# J3.net
KiCad netlist of a schematic drawn in Altium Designer
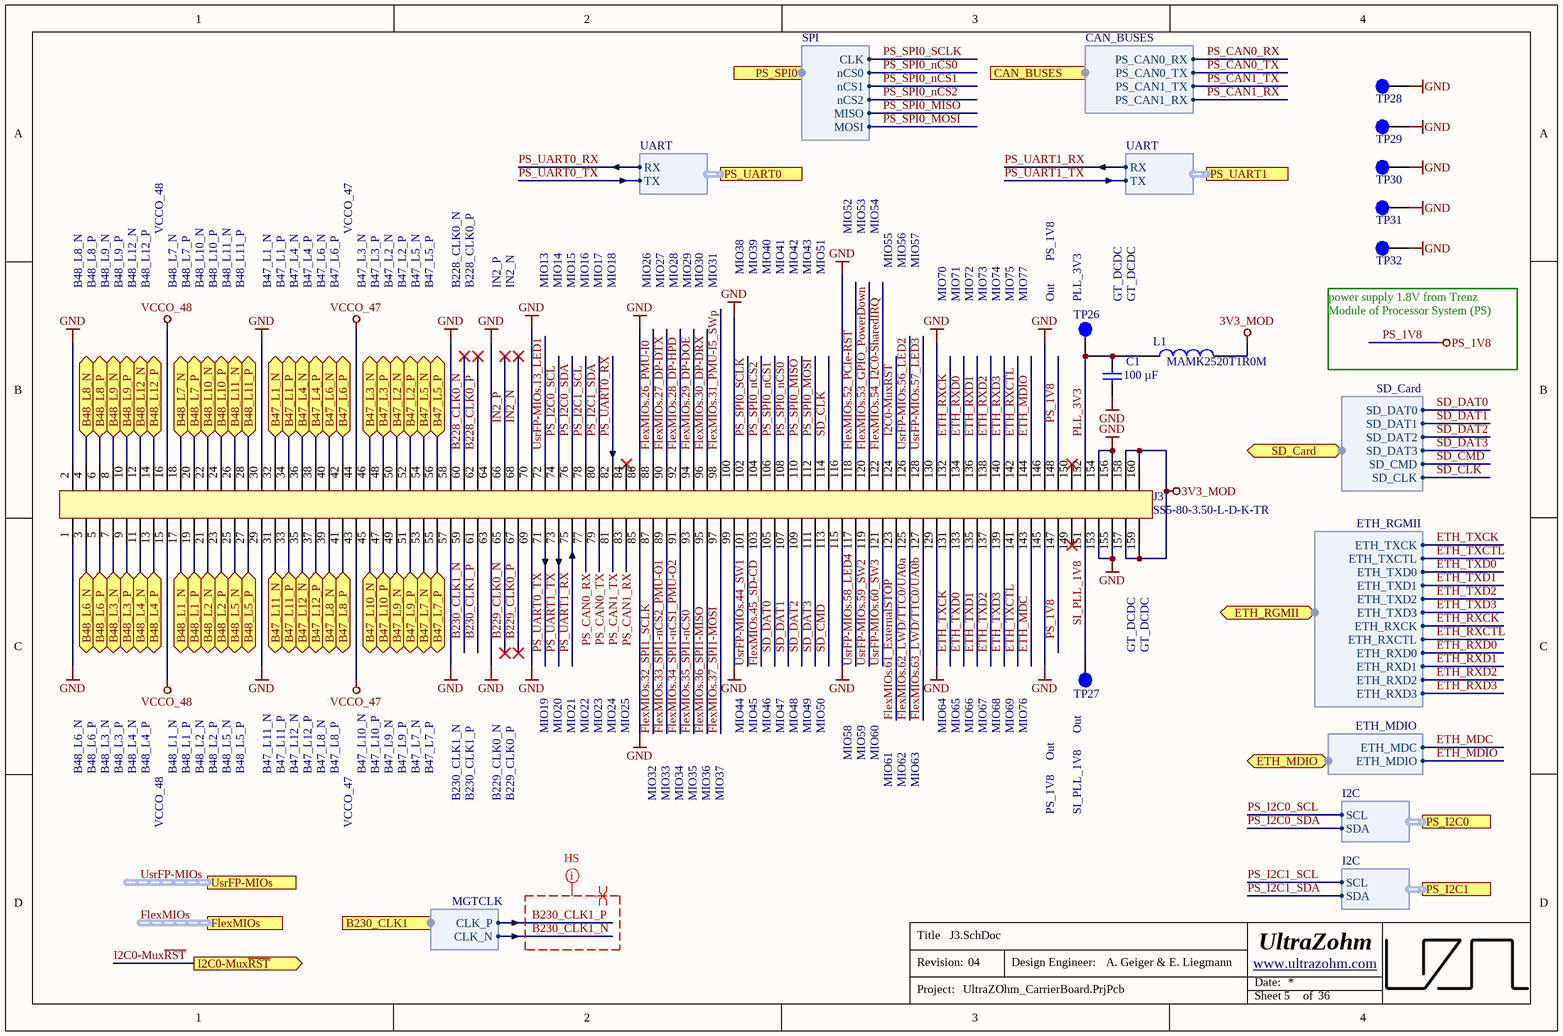
[diagram p0: J3.SchDoc]

(export (version "E")
  (design (tool "Eeschema 10.0.6"))
  (components
    (comp (ref "C1")
      (value "100 µF")
      (footprint "C_1206_TE")
      (description "6.3V 100uF X5R ±20% 1206 Multilayer Ceramic Capacitors MLCC")
      (fields
        (field (name "TOLERANCE") "20%")
        (field (name "MANUFACTURER PART NUMBER") "CL31A107MQHNNNE")
        (field (name "CREATED FROM") "MGeier")
      )
      (libsource (lib "user") (part "CAP-NP"))
    )
    (comp (ref "J3")
      (value "SS5-80-3.50-L-D-K-TR")
      (footprint "SS5-80-3.50-L-D-K-TR")
      (description "0.5 mm Ultra Fine Pitch Socket REF192552-01, 160 Pins")
      (fields
        (field (name "MANUFACTURER") "SAMTEC")
        (field (name "LCSC PART NUMBER") "C5292077")
        (field (name "CREATED FROM") "MGremer")
      )
      (libsource (lib "user") (part "SS5-80-3.50-L-D-K-TR"))
    )
    (comp (ref "L1")
      (value "MAMK2520T1R0M")
      (footprint "INDC2520X120N")
      (description "1uH @2MHz ±20%, 2.7A, 59mOhm, 5040")
      (fields
        (field (name "MF") "EPCOS / TDK")
        (field (name "MPN") "B82464G4154M")
        (field (name "CREATED FROM") "FRosner")
      )
      (libsource (lib "user") (part "B82464G4154M"))
    )
    (comp (ref "TP26") (value "Testpoint 1mm") (footprint "TP_1mm") (libsource (lib "TE") (part "TP")))
    (comp (ref "TP27") (value "Testpoint 1mm") (footprint "TP_1mm") (libsource (lib "TE") (part "TP")))
    (comp (ref "TP28") (value "Testpoint 1mm") (footprint "TP_1mm") (libsource (lib "TE") (part "TP")))
    (comp (ref "TP29") (value "Testpoint 1mm") (footprint "TP_1mm") (libsource (lib "TE") (part "TP")))
    (comp (ref "TP30") (value "Testpoint 1mm") (footprint "TP_1mm") (libsource (lib "TE") (part "TP")))
    (comp (ref "TP31") (value "Testpoint 1mm") (footprint "TP_1mm") (libsource (lib "TE") (part "TP")))
    (comp (ref "TP32") (value "Testpoint 1mm") (footprint "TP_1mm") (libsource (lib "TE") (part "TP")))
  )
  (nets
    (net (code "10") (name "/B47_L1_N") (class "Default")
      (node (ref "J3") (pin "32") (pinfunction "32_32") (pintype "passive"))
    )
    (net (code "11") (name "/B47_L1_P") (class "Default")
      (node (ref "J3") (pin "34") (pinfunction "34_34") (pintype "passive"))
    )
    (net (code "12") (name "/B47_L2_N") (class "Default")
      (node (ref "J3") (pin "50") (pinfunction "50_50") (pintype "passive"))
    )
    (net (code "13") (name "/B47_L2_P") (class "Default")
      (node (ref "J3") (pin "52") (pinfunction "52_52") (pintype "passive"))
    )
    (net (code "14") (name "/B47_L3_N") (class "Default")
      (node (ref "J3") (pin "46") (pinfunction "46_46") (pintype "passive"))
    )
    (net (code "15") (name "/B47_L3_P") (class "Default")
      (node (ref "J3") (pin "48") (pinfunction "48_48") (pintype "passive"))
    )
    (net (code "16") (name "/B47_L4_N") (class "Default")
      (node (ref "J3") (pin "36") (pinfunction "36_36") (pintype "passive"))
    )
    (net (code "17") (name "/B47_L4_P") (class "Default")
      (node (ref "J3") (pin "38") (pinfunction "38_38") (pintype "passive"))
    )
    (net (code "18") (name "/B47_L5_N") (class "Default")
      (node (ref "J3") (pin "54") (pinfunction "54_54") (pintype "passive"))
    )
    (net (code "19") (name "/B47_L5_P") (class "Default")
      (node (ref "J3") (pin "56") (pinfunction "56_56") (pintype "passive"))
    )
    (net (code "20") (name "/B47_L6_N") (class "Default")
      (node (ref "J3") (pin "40") (pinfunction "40_40") (pintype "passive"))
    )
    (net (code "21") (name "/B47_L6_P") (class "Default")
      (node (ref "J3") (pin "42") (pinfunction "42_42") (pintype "passive"))
    )
    (net (code "22") (name "/B47_L7_N") (class "Default")
      (node (ref "J3") (pin "53") (pinfunction "53_53") (pintype "passive"))
    )
    (net (code "23") (name "/B47_L7_P") (class "Default")
      (node (ref "J3") (pin "55") (pinfunction "55_55") (pintype "passive"))
    )
    (net (code "24") (name "/B47_L8_N") (class "Default")
      (node (ref "J3") (pin "39") (pinfunction "39_39") (pintype "passive"))
    )
    (net (code "25") (name "/B47_L8_P") (class "Default")
      (node (ref "J3") (pin "41") (pinfunction "41_41") (pintype "passive"))
    )
    (net (code "26") (name "/B47_L9_N") (class "Default")
      (node (ref "J3") (pin "49") (pinfunction "49_49") (pintype "passive"))
    )
    (net (code "27") (name "/B47_L9_P") (class "Default")
      (node (ref "J3") (pin "51") (pinfunction "51_51") (pintype "passive"))
    )
    (net (code "28") (name "/B47_L10_N") (class "Default")
      (node (ref "J3") (pin "45") (pinfunction "45_45") (pintype "passive"))
    )
    (net (code "29") (name "/B47_L10_P") (class "Default")
      (node (ref "J3") (pin "47") (pinfunction "47_47") (pintype "passive"))
    )
    (net (code "30") (name "/B47_L11_N") (class "Default")
      (node (ref "J3") (pin "31") (pinfunction "31_31") (pintype "passive"))
    )
    (net (code "31") (name "/B47_L11_P") (class "Default")
      (node (ref "J3") (pin "33") (pinfunction "33_33") (pintype "passive"))
    )
    (net (code "32") (name "/B47_L12_N") (class "Default")
      (node (ref "J3") (pin "35") (pinfunction "35_35") (pintype "passive"))
    )
    (net (code "33") (name "/B47_L12_P") (class "Default")
      (node (ref "J3") (pin "37") (pinfunction "37_37") (pintype "passive"))
    )
    (net (code "34") (name "/B48_L1_N") (class "Default")
      (node (ref "J3") (pin "17") (pinfunction "17_17") (pintype "passive"))
    )
    (net (code "35") (name "/B48_L1_P") (class "Default")
      (node (ref "J3") (pin "19") (pinfunction "19_19") (pintype "passive"))
    )
    (net (code "36") (name "/B48_L2_N") (class "Default")
      (node (ref "J3") (pin "21") (pinfunction "21_21") (pintype "passive"))
    )
    (net (code "37") (name "/B48_L2_P") (class "Default")
      (node (ref "J3") (pin "23") (pinfunction "23_23") (pintype "passive"))
    )
    (net (code "38") (name "/B48_L3_N") (class "Default")
      (node (ref "J3") (pin "7") (pinfunction "7_7") (pintype "passive"))
    )
    (net (code "39") (name "/B48_L3_P") (class "Default")
      (node (ref "J3") (pin "9") (pinfunction "9_9") (pintype "passive"))
    )
    (net (code "40") (name "/B48_L4_N") (class "Default")
      (node (ref "J3") (pin "11") (pinfunction "11_11") (pintype "passive"))
    )
    (net (code "41") (name "/B48_L4_P") (class "Default")
      (node (ref "J3") (pin "13") (pinfunction "13_13") (pintype "passive"))
    )
    (net (code "42") (name "/B48_L5_N") (class "Default")
      (node (ref "J3") (pin "25") (pinfunction "25_25") (pintype "passive"))
    )
    (net (code "43") (name "/B48_L5_P") (class "Default")
      (node (ref "J3") (pin "27") (pinfunction "27_27") (pintype "passive"))
    )
    (net (code "44") (name "/B48_L6_N") (class "Default")
      (node (ref "J3") (pin "3") (pinfunction "3_3") (pintype "passive"))
    )
    (net (code "45") (name "/B48_L6_P") (class "Default")
      (node (ref "J3") (pin "5") (pinfunction "5_5") (pintype "passive"))
    )
    (net (code "46") (name "/B48_L7_N") (class "Default")
      (node (ref "J3") (pin "18") (pinfunction "18_18") (pintype "passive"))
    )
    (net (code "47") (name "/B48_L7_P") (class "Default")
      (node (ref "J3") (pin "20") (pinfunction "20_20") (pintype "passive"))
    )
    (net (code "48") (name "/B48_L8_N") (class "Default")
      (node (ref "J3") (pin "4") (pinfunction "4_4") (pintype "passive"))
    )
    (net (code "49") (name "/B48_L8_P") (class "Default")
      (node (ref "J3") (pin "6") (pinfunction "6_6") (pintype "passive"))
    )
    (net (code "50") (name "/B48_L9_N") (class "Default")
      (node (ref "J3") (pin "8") (pinfunction "8_8") (pintype "passive"))
    )
    (net (code "51") (name "/B48_L9_P") (class "Default")
      (node (ref "J3") (pin "10") (pinfunction "10_10") (pintype "passive"))
    )
    (net (code "52") (name "/B48_L10_N") (class "Default")
      (node (ref "J3") (pin "22") (pinfunction "22_22") (pintype "passive"))
    )
    (net (code "53") (name "/B48_L10_P") (class "Default")
      (node (ref "J3") (pin "24") (pinfunction "24_24") (pintype "passive"))
    )
    (net (code "54") (name "/B48_L11_N") (class "Default")
      (node (ref "J3") (pin "26") (pinfunction "26_26") (pintype "passive"))
    )
    (net (code "55") (name "/B48_L11_P") (class "Default")
      (node (ref "J3") (pin "28") (pinfunction "28_28") (pintype "passive"))
    )
    (net (code "56") (name "/B48_L12_N") (class "Default")
      (node (ref "J3") (pin "12") (pinfunction "12_12") (pintype "passive"))
    )
    (net (code "57") (name "/B48_L12_P") (class "Default")
      (node (ref "J3") (pin "14") (pinfunction "14_14") (pintype "passive"))
    )
    (net (code "58") (name "/B228_CLK0_N") (class "Default")
      (node (ref "J3") (pin "60") (pinfunction "60_60") (pintype "passive+no_connect"))
    )
    (net (code "59") (name "/B228_CLK0_P") (class "Default")
      (node (ref "J3") (pin "62") (pinfunction "62_62") (pintype "passive+no_connect"))
    )
    (net (code "60") (name "/B229_CLK0_N") (class "Default")
      (node (ref "J3") (pin "65") (pinfunction "65_65") (pintype "passive+no_connect"))
    )
    (net (code "61") (name "/B229_CLK0_P") (class "Default")
      (node (ref "J3") (pin "67") (pinfunction "67_67") (pintype "passive+no_connect"))
    )
    (net (code "62") (name "/B230_CLK1_N") (class "Default")
      (node (ref "J3") (pin "59") (pinfunction "59_59") (pintype "passive"))
    )
    (net (code "63") (name "/B230_CLK1_P") (class "Default")
      (node (ref "J3") (pin "61") (pinfunction "61_61") (pintype "passive"))
    )
    (net (code "64") (name "/ETH_MDC") (class "Default")
      (node (ref "J3") (pin "143") (pinfunction "143_143") (pintype "passive"))
    )
    (net (code "65") (name "/ETH_MDIO") (class "Default")
      (node (ref "J3") (pin "144") (pinfunction "144_144") (pintype "passive"))
    )
    (net (code "66") (name "/ETH_RXCK") (class "Default")
      (node (ref "J3") (pin "132") (pinfunction "132_132") (pintype "passive"))
    )
    (net (code "67") (name "/ETH_RXCTL") (class "Default")
      (node (ref "J3") (pin "142") (pinfunction "142_142") (pintype "passive"))
    )
    (net (code "68") (name "/ETH_RXD0") (class "Default")
      (node (ref "J3") (pin "134") (pinfunction "134_134") (pintype "passive"))
    )
    (net (code "69") (name "/ETH_RXD1") (class "Default")
      (node (ref "J3") (pin "136") (pinfunction "136_136") (pintype "passive"))
    )
    (net (code "70") (name "/ETH_RXD2") (class "Default")
      (node (ref "J3") (pin "138") (pinfunction "138_138") (pintype "passive"))
    )
    (net (code "71") (name "/ETH_RXD3") (class "Default")
      (node (ref "J3") (pin "140") (pinfunction "140_140") (pintype "passive"))
    )
    (net (code "72") (name "/ETH_TXCK") (class "Default")
      (node (ref "J3") (pin "131") (pinfunction "131_131") (pintype "passive"))
    )
    (net (code "73") (name "/ETH_TXCTL") (class "Default")
      (node (ref "J3") (pin "141") (pinfunction "141_141") (pintype "passive"))
    )
    (net (code "74") (name "/ETH_TXD0") (class "Default")
      (node (ref "J3") (pin "133") (pinfunction "133_133") (pintype "passive"))
    )
    (net (code "75") (name "/ETH_TXD1") (class "Default")
      (node (ref "J3") (pin "135") (pinfunction "135_135") (pintype "passive"))
    )
    (net (code "76") (name "/ETH_TXD2") (class "Default")
      (node (ref "J3") (pin "137") (pinfunction "137_137") (pintype "passive"))
    )
    (net (code "77") (name "/ETH_TXD3") (class "Default")
      (node (ref "J3") (pin "139") (pinfunction "139_139") (pintype "passive"))
    )
    (net (code "78") (name "/FlexMIOs.26_PMU-I0") (class "Default")
      (node (ref "J3") (pin "88") (pinfunction "88_88") (pintype "passive"))
    )
    (net (code "79") (name "/FlexMIOs.27_DP-DTX") (class "Default")
      (node (ref "J3") (pin "90") (pinfunction "90_90") (pintype "passive"))
    )
    (net (code "80") (name "/FlexMIOs.28_DP-HPD") (class "Default")
      (node (ref "J3") (pin "92") (pinfunction "92_92") (pintype "passive"))
    )
    (net (code "81") (name "/FlexMIOs.29_DP-DOE") (class "Default")
      (node (ref "J3") (pin "94") (pinfunction "94_94") (pintype "passive"))
    )
    (net (code "82") (name "/FlexMIOs.30_DP-DRX") (class "Default")
      (node (ref "J3") (pin "96") (pinfunction "96_96") (pintype "passive"))
    )
    (net (code "83") (name "/FlexMIOs.31_PMU-I5_SWp") (class "Default")
      (node (ref "J3") (pin "98") (pinfunction "98_98") (pintype "passive"))
    )
    (net (code "84") (name "/FlexMIOs.32_SPI1_SCLK") (class "Default")
      (node (ref "J3") (pin "87") (pinfunction "87_87") (pintype "passive"))
    )
    (net (code "85") (name "/FlexMIOs.33_SPI1-nCS2_PMU-O1") (class "Default")
      (node (ref "J3") (pin "89") (pinfunction "89_89") (pintype "passive"))
    )
    (net (code "86") (name "/FlexMIOs.34_SPI1-nCS1_PMU-O2") (class "Default")
      (node (ref "J3") (pin "91") (pinfunction "91_91") (pintype "passive"))
    )
    (net (code "87") (name "/FlexMIOs.35_SPI1-nCS0") (class "Default")
      (node (ref "J3") (pin "93") (pinfunction "93_93") (pintype "passive"))
    )
    (net (code "88") (name "/FlexMIOs.36_SPI1-MISO") (class "Default")
      (node (ref "J3") (pin "95") (pinfunction "95_95") (pintype "passive"))
    )
    (net (code "89") (name "/FlexMIOs.37_SPI1-MOSI") (class "Default")
      (node (ref "J3") (pin "97") (pinfunction "97_97") (pintype "passive"))
    )
    (net (code "90") (name "/FlexMIOs.45_SD-CD") (class "Default")
      (node (ref "J3") (pin "103") (pinfunction "103_103") (pintype "passive"))
    )
    (net (code "91") (name "/FlexMIOs.52_PCIe-~{RST}") (class "Default")
      (node (ref "J3") (pin "118") (pinfunction "118_118") (pintype "passive"))
    )
    (net (code "92") (name "/FlexMIOs.53_GPIO_PowerDown") (class "Default")
      (node (ref "J3") (pin "120") (pinfunction "120_120") (pintype "passive"))
    )
    (net (code "93") (name "/FlexMIOs.54_I2C0-Shared~{IRQ}") (class "Default")
      (node (ref "J3") (pin "122") (pinfunction "122_122") (pintype "passive"))
    )
    (net (code "94") (name "/FlexMIOs.61_ExternalSTOP") (class "Default")
      (node (ref "J3") (pin "123") (pinfunction "123_123") (pintype "passive"))
    )
    (net (code "95") (name "/FlexMIOs.62_LWD{slash}TTC0{slash}UA0a") (class "Default")
      (node (ref "J3") (pin "125") (pinfunction "125_125") (pintype "passive"))
    )
    (net (code "96") (name "/FlexMIOs.63_LWD{slash}TTC0{slash}UA0b") (class "Default")
      (node (ref "J3") (pin "127") (pinfunction "127_127") (pintype "passive"))
    )
    (net (code "97") (name "/I2C0-Mux~{RST}") (class "Default")
      (node (ref "J3") (pin "124") (pinfunction "124_124") (pintype "passive"))
    )
    (net (code "98") (name "/IN2_N") (class "Default")
      (node (ref "J3") (pin "68") (pinfunction "68_68") (pintype "passive+no_connect"))
    )
    (net (code "99") (name "/IN2_P") (class "Default")
      (node (ref "J3") (pin "66") (pinfunction "66_66") (pintype "passive+no_connect"))
    )
    (net (code "100") (name "/PLL_3V3") (class "Default")
      (node (ref "C1") (pin "1") (pinfunction "1_1") (pintype "passive"))
      (node (ref "J3") (pin "152") (pinfunction "152_152") (pintype "passive"))
      (node (ref "L1") (pin "1") (pinfunction "1_1") (pintype "passive"))
      (node (ref "TP26") (pin "1") (pintype "passive"))
    )
    (net (code "101") (name "/PS_CAN0_RX") (class "Default")
      (node (ref "J3") (pin "77") (pinfunction "77_77") (pintype "passive"))
    )
    (net (code "102") (name "/PS_CAN0_TX") (class "Default")
      (node (ref "J3") (pin "79") (pinfunction "79_79") (pintype "passive"))
    )
    (net (code "103") (name "/PS_CAN1_RX") (class "Default")
      (node (ref "J3") (pin "83") (pinfunction "83_83") (pintype "passive"))
    )
    (net (code "104") (name "/PS_CAN1_TX") (class "Default")
      (node (ref "J3") (pin "81") (pinfunction "81_81") (pintype "passive"))
    )
    (net (code "105") (name "/PS_I2C0_SCL") (class "Default")
      (node (ref "J3") (pin "74") (pinfunction "74_74") (pintype "passive"))
    )
    (net (code "106") (name "/PS_I2C0_SDA") (class "Default")
      (node (ref "J3") (pin "76") (pinfunction "76_76") (pintype "passive"))
    )
    (net (code "107") (name "/PS_I2C1_SCL") (class "Default")
      (node (ref "J3") (pin "78") (pinfunction "78_78") (pintype "passive"))
    )
    (net (code "108") (name "/PS_I2C1_SDA") (class "Default")
      (node (ref "J3") (pin "80") (pinfunction "80_80") (pintype "passive"))
    )
    (net (code "109") (name "/PS_SPI0_MISO") (class "Default")
      (node (ref "J3") (pin "110") (pinfunction "110_110") (pintype "passive"))
    )
    (net (code "110") (name "/PS_SPI0_MOSI") (class "Default")
      (node (ref "J3") (pin "112") (pinfunction "112_112") (pintype "passive"))
    )
    (net (code "111") (name "/PS_SPI0_SCLK") (class "Default")
      (node (ref "J3") (pin "102") (pinfunction "102_102") (pintype "passive"))
    )
    (net (code "112") (name "/PS_SPI0_nCS0") (class "Default")
      (node (ref "J3") (pin "108") (pinfunction "108_108") (pintype "passive"))
    )
    (net (code "113") (name "/PS_SPI0_nCS1") (class "Default")
      (node (ref "J3") (pin "106") (pinfunction "106_106") (pintype "passive"))
    )
    (net (code "114") (name "/PS_SPI0_nCS2") (class "Default")
      (node (ref "J3") (pin "104") (pinfunction "104_104") (pintype "passive"))
    )
    (net (code "115") (name "/PS_UART0_RX") (class "Default")
      (node (ref "J3") (pin "82") (pinfunction "82_82") (pintype "passive"))
    )
    (net (code "116") (name "/PS_UART0_TX") (class "Default")
      (node (ref "J3") (pin "71") (pinfunction "71_71") (pintype "passive"))
    )
    (net (code "117") (name "/PS_UART1_RX") (class "Default")
      (node (ref "J3") (pin "75") (pinfunction "75_75") (pintype "passive"))
    )
    (net (code "118") (name "/PS_UART1_TX") (class "Default")
      (node (ref "J3") (pin "73") (pinfunction "73_73") (pintype "passive"))
    )
    (net (code "119") (name "/SD_CLK") (class "Default")
      (node (ref "J3") (pin "114") (pinfunction "114_114") (pintype "passive"))
    )
    (net (code "120") (name "/SD_CMD") (class "Default")
      (node (ref "J3") (pin "113") (pinfunction "113_113") (pintype "passive"))
    )
    (net (code "121") (name "/SD_DAT0") (class "Default")
      (node (ref "J3") (pin "105") (pinfunction "105_105") (pintype "passive"))
    )
    (net (code "122") (name "/SD_DAT1") (class "Default")
      (node (ref "J3") (pin "107") (pinfunction "107_107") (pintype "passive"))
    )
    (net (code "123") (name "/SD_DAT2") (class "Default")
      (node (ref "J3") (pin "109") (pinfunction "109_109") (pintype "passive"))
    )
    (net (code "124") (name "/SD_DAT3") (class "Default")
      (node (ref "J3") (pin "111") (pinfunction "111_111") (pintype "passive"))
    )
    (net (code "125") (name "/SI_PLL_1V8") (class "Default")
      (node (ref "J3") (pin "151") (pinfunction "151_151") (pintype "passive"))
      (node (ref "TP27") (pin "1") (pintype "passive"))
    )
    (net (code "126") (name "/UsrFP-MIOs.13_LED1") (class "Default")
      (node (ref "J3") (pin "72") (pinfunction "72_72") (pintype "passive"))
    )
    (net (code "127") (name "/UsrFP-MIOs.44_SW1") (class "Default")
      (node (ref "J3") (pin "101") (pinfunction "101_101") (pintype "passive"))
    )
    (net (code "128") (name "/UsrFP-MIOs.56_LED2") (class "Default")
      (node (ref "J3") (pin "126") (pinfunction "126_126") (pintype "passive"))
    )
    (net (code "129") (name "/UsrFP-MIOs.57_LED3") (class "Default")
      (node (ref "J3") (pin "128") (pinfunction "128_128") (pintype "passive"))
    )
    (net (code "130") (name "/UsrFP-MIOs.58_LED4") (class "Default")
      (node (ref "J3") (pin "117") (pinfunction "117_117") (pintype "passive"))
    )
    (net (code "131") (name "/UsrFP-MIOs.59_SW2") (class "Default")
      (node (ref "J3") (pin "119") (pinfunction "119_119") (pintype "passive"))
    )
    (net (code "132") (name "/UsrFP-MIOs.60_SW3") (class "Default")
      (node (ref "J3") (pin "121") (pinfunction "121_121") (pintype "passive"))
    )
    (net (code "143") (name "3V3_MOD") (class "Default")
      (node (ref "J3") (pin "157") (pinfunction "157_157") (pintype "passive"))
      (node (ref "J3") (pin "158") (pinfunction "158_158") (pintype "passive"))
      (node (ref "J3") (pin "159") (pinfunction "159_159") (pintype "passive"))
      (node (ref "J3") (pin "160") (pinfunction "160_160") (pintype "passive"))
      (node (ref "L1") (pin "2") (pinfunction "2_2") (pintype "passive"))
    )
    (net (code "144") (name "GND") (class "Default")
      (node (ref "C1") (pin "2") (pinfunction "2_2") (pintype "passive"))
      (node (ref "J3") (pin "1") (pinfunction "1_1") (pintype "passive"))
      (node (ref "J3") (pin "100") (pinfunction "100_100") (pintype "passive"))
      (node (ref "J3") (pin "115") (pinfunction "115_115") (pintype "passive"))
      (node (ref "J3") (pin "116") (pinfunction "116_116") (pintype "passive"))
      (node (ref "J3") (pin "129") (pinfunction "129_129") (pintype "passive"))
      (node (ref "J3") (pin "130") (pinfunction "130_130") (pintype "passive"))
      (node (ref "J3") (pin "145") (pinfunction "145_145") (pintype "passive"))
      (node (ref "J3") (pin "146") (pinfunction "146_146") (pintype "passive"))
      (node (ref "J3") (pin "153") (pinfunction "153_153") (pintype "passive"))
      (node (ref "J3") (pin "154") (pinfunction "154_154") (pintype "passive"))
      (node (ref "J3") (pin "155") (pinfunction "155_155") (pintype "passive"))
      (node (ref "J3") (pin "156") (pinfunction "156_156") (pintype "passive"))
      (node (ref "J3") (pin "2") (pinfunction "2_2") (pintype "passive"))
      (node (ref "J3") (pin "29") (pinfunction "29_29") (pintype "passive"))
      (node (ref "J3") (pin "30") (pinfunction "30_30") (pintype "passive"))
      (node (ref "J3") (pin "57") (pinfunction "57_57") (pintype "passive"))
      (node (ref "J3") (pin "58") (pinfunction "58_58") (pintype "passive"))
      (node (ref "J3") (pin "63") (pinfunction "63_63") (pintype "passive"))
      (node (ref "J3") (pin "64") (pinfunction "64_64") (pintype "passive"))
      (node (ref "J3") (pin "69") (pinfunction "69_69") (pintype "passive"))
      (node (ref "J3") (pin "70") (pinfunction "70_70") (pintype "passive"))
      (node (ref "J3") (pin "85") (pinfunction "85_85") (pintype "passive"))
      (node (ref "J3") (pin "86") (pinfunction "86_86") (pintype "passive"))
      (node (ref "J3") (pin "99") (pinfunction "99_99") (pintype "passive"))
      (node (ref "TP28") (pin "1") (pintype "passive"))
      (node (ref "TP29") (pin "1") (pintype "passive"))
      (node (ref "TP30") (pin "1") (pintype "passive"))
      (node (ref "TP31") (pin "1") (pintype "passive"))
      (node (ref "TP32") (pin "1") (pintype "passive"))
    )
    (net (code "145") (name "PS_1V8") (class "Default")
      (node (ref "J3") (pin "147") (pinfunction "147_147") (pintype "passive"))
      (node (ref "J3") (pin "148") (pinfunction "148_148") (pintype "passive"))
    )
    (net (code "146") (name "VCCO_47") (class "Default")
      (node (ref "J3") (pin "43") (pinfunction "43_43") (pintype "passive"))
      (node (ref "J3") (pin "44") (pinfunction "44_44") (pintype "passive"))
    )
    (net (code "147") (name "VCCO_48") (class "Default")
      (node (ref "J3") (pin "15") (pinfunction "15_15") (pintype "passive"))
      (node (ref "J3") (pin "16") (pinfunction "16_16") (pintype "passive"))
    )
    (net (code "148") (name "unconnected-(J3-Pad84)") (class "Default")
      (node (ref "J3") (pin "84") (pinfunction "84_84") (pintype "passive+no_connect"))
    )
    (net (code "149") (name "unconnected-(J3-Pad149)") (class "Default")
      (node (ref "J3") (pin "149") (pinfunction "149_149") (pintype "passive+no_connect"))
    )
    (net (code "150") (name "unconnected-(J3-Pad150)") (class "Default")
      (node (ref "J3") (pin "150") (pinfunction "150_150") (pintype "passive+no_connect"))
    )
  )
)
